# Pluvion_2_-_Rev_B.net
KiCad netlist of a schematic drawn in EAGLE
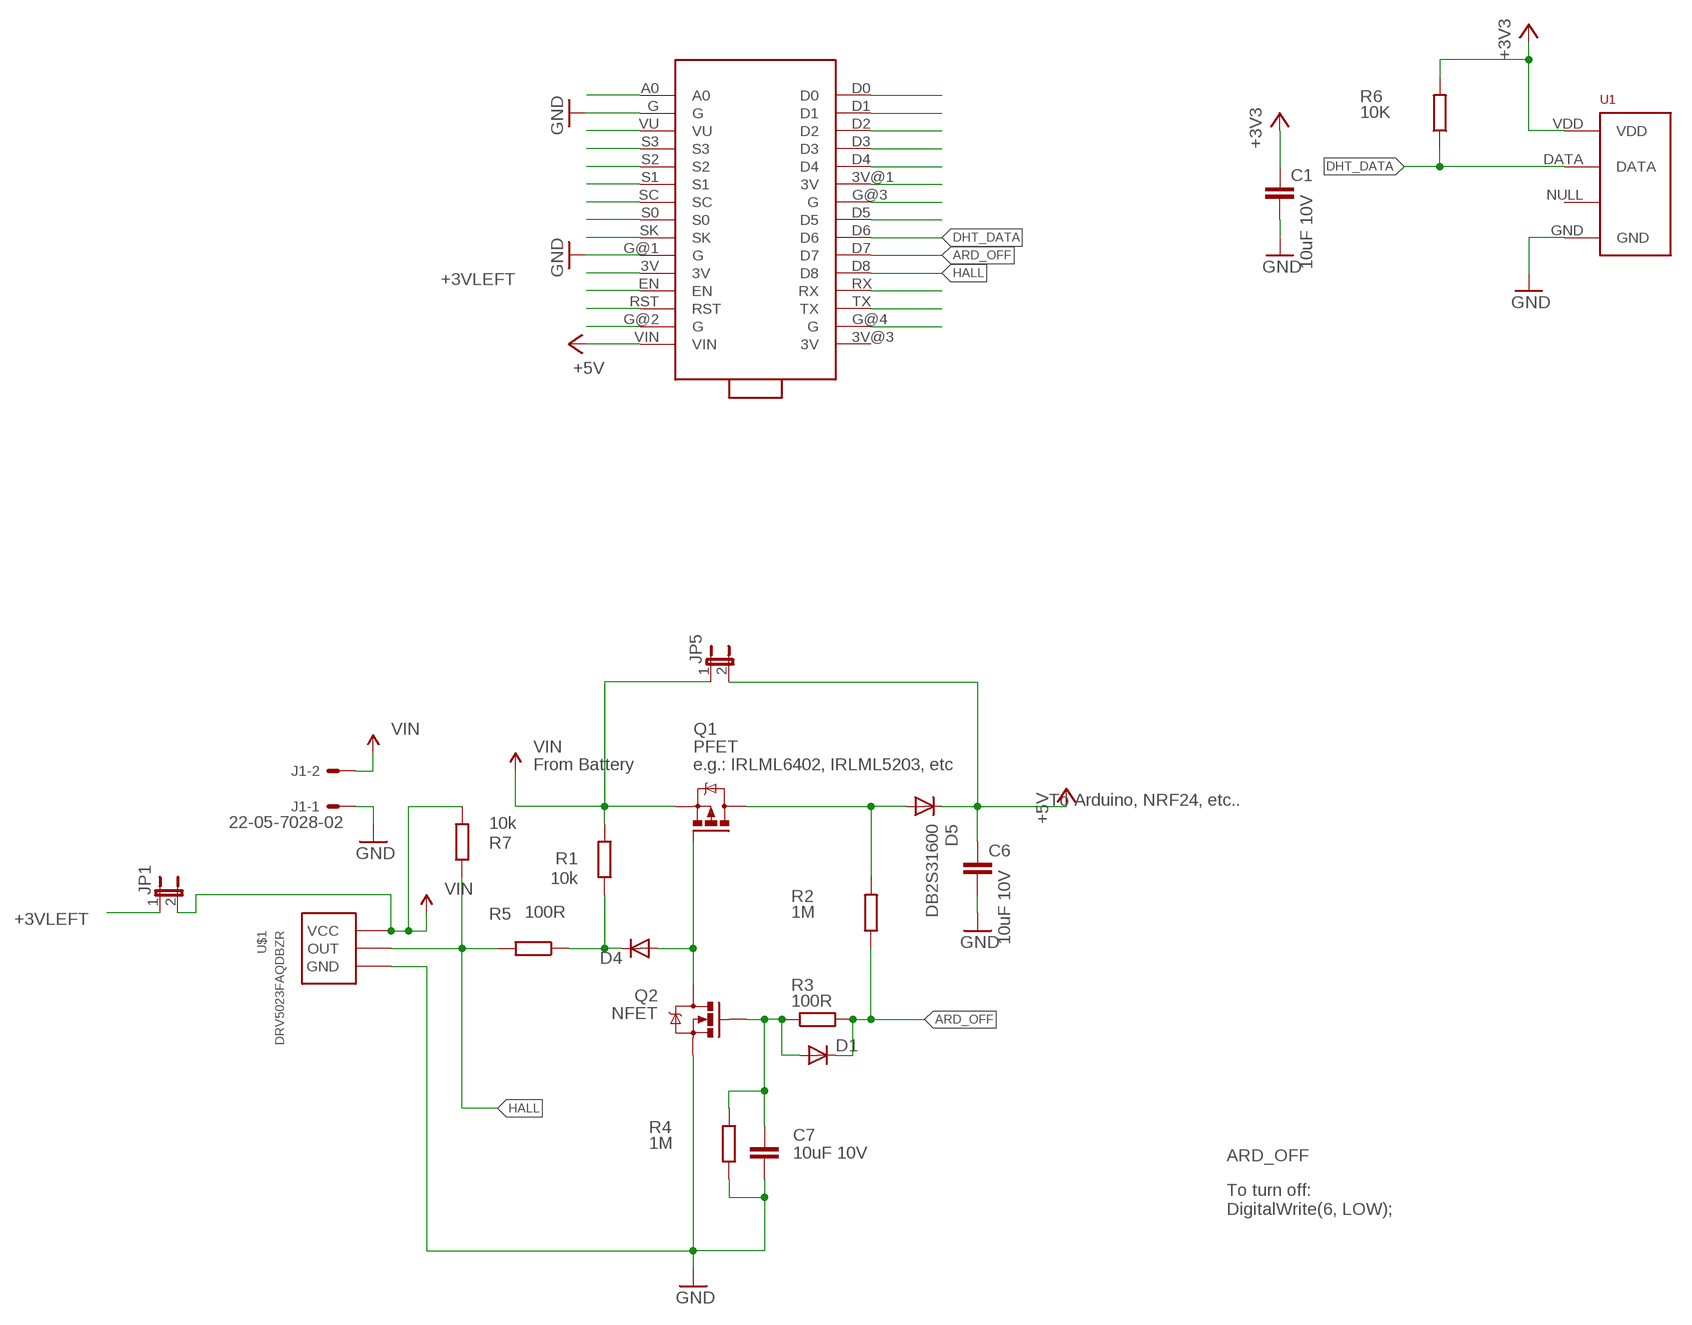
[diagram p0: schematic, sheet 1]

(export (version "E")
  (design (tool "Eeschema 10.0.6"))
  (components
    (comp (ref "C1")
      (value "10uF 10V")
      (footprint "eagle-import:C0805")
      (libsource (lib "eagle-import") (part "C-EUC0805"))
    )
    (comp (ref "C6")
      (value "10uF 10V")
      (footprint "eagle-import:C0805")
      (libsource (lib "eagle-import") (part "C-EUC0805"))
    )
    (comp (ref "C7")
      (value "10uF 10V")
      (footprint "eagle-import:C0805")
      (libsource (lib "eagle-import") (part "C-EUC0805"))
    )
    (comp (ref "D1")
      (value "DIODESOD")
      (footprint "eagle-import:SOD-323")
      (libsource (lib "eagle-import") (part "DIODESOD"))
    )
    (comp (ref "D4")
      (value "DIODESOD")
      (footprint "eagle-import:SOD-323")
      (libsource (lib "eagle-import") (part "DIODESOD"))
    )
    (comp (ref "D5")
      (value "DB2S31600")
      (footprint "eagle-import:SMA-DIODE")
      (libsource (lib "eagle-import") (part "DIODESMA"))
    )
    (comp (ref "J1")
      (value "22-05-7028-02")
      (footprint "eagle-import:7395-02")
      (libsource (lib "eagle-import") (part "22-?-0205-7028"))
    )
    (comp (ref "JP1")
      (value "JUMPER-2PTH")
      (footprint "eagle-import:1X02")
      (libsource (lib "eagle-import") (part "JUMPER-2PTH"))
    )
    (comp (ref "JP5")
      (value "JUMPER-2PTH")
      (footprint "eagle-import:1X02")
      (libsource (lib "eagle-import") (part "JUMPER-2PTH"))
    )
    (comp (ref "Q1")
      (value "PFET")
      (footprint "eagle-import:MICRO3")
      (libsource (lib "eagle-import") (part "IRLML5203"))
    )
    (comp (ref "Q2")
      (value "NFET")
      (footprint "eagle-import:SOT23")
      (libsource (lib "eagle-import") (part "MOSFET-NCHANNELBSS123LT1G"))
    )
    (comp (ref "R1")
      (value "10k")
      (footprint "eagle-import:R0805")
      (libsource (lib "eagle-import") (part "R-EU_R0805"))
    )
    (comp (ref "R2")
      (value "1M")
      (footprint "eagle-import:R0805")
      (libsource (lib "eagle-import") (part "R-EU_R0805"))
    )
    (comp (ref "R3")
      (value "100R")
      (footprint "eagle-import:R0805")
      (libsource (lib "eagle-import") (part "R-EU_R0805"))
    )
    (comp (ref "R4")
      (value "1M")
      (footprint "eagle-import:R0805")
      (libsource (lib "eagle-import") (part "R-EU_R0805"))
    )
    (comp (ref "R5")
      (value "100R")
      (footprint "eagle-import:R0805")
      (libsource (lib "eagle-import") (part "R-EU_R0805"))
    )
    (comp (ref "R6")
      (value "10K")
      (footprint "eagle-import:R0805")
      (libsource (lib "eagle-import") (part "R-EU_R0805"))
    )
    (comp (ref "R7")
      (value "10k")
      (footprint "eagle-import:R0805")
      (libsource (lib "eagle-import") (part "R-EU_R0805"))
    )
    (comp (ref "U$1")
      (value "DRV5023FAQDBZR")
      (footprint "eagle-import:SOT23")
      (libsource (lib "eagle-import") (part "DRV5023FAQDBZR"))
    )
    (comp (ref "U$2")
      (value "NODE-LOLIN-ESP8266")
      (footprint "eagle-import:NODE-LOLIN-ESP8266")
      (libsource (lib "eagle-import") (part "NODE-LOLIN-ESP8266"))
    )
    (comp (ref "U1")
      (value "RHT03_DHT-22_AM2302RA")
      (footprint "eagle-import:RHT03_DHT-22_RA")
      (libsource (lib "eagle-import") (part "RHT03_DHT-22_AM2302RA"))
    )
  )
  (nets
    (net (code "1") (name "+3V3") (class "Default")
      (node (ref "C1") (pin "1") (pinfunction "1_1") (pintype "passive"))
      (node (ref "R6") (pin "2") (pinfunction "2_2") (pintype "passive"))
      (node (ref "U$2") (pin "3V@1") (pinfunction "3V_3V@1") (pintype "bidirectional"))
      (node (ref "U1") (pin "VDD") (pinfunction "VDD_VDD") (pintype "power_in"))
    )
    (net (code "2") (name "+3VLEFT") (class "Default")
      (node (ref "JP1") (pin "1") (pinfunction "1_1") (pintype "passive"))
      (node (ref "U$2") (pin "3V") (pinfunction "3V_3V") (pintype "bidirectional"))
    )
    (net (code "3") (name "+5V") (class "Default")
      (node (ref "C6") (pin "1") (pinfunction "1_1") (pintype "passive"))
      (node (ref "D5") (pin "C") (pinfunction "C_C") (pintype "passive"))
      (node (ref "JP5") (pin "2") (pinfunction "2_2") (pintype "passive"))
      (node (ref "U$2") (pin "VIN") (pinfunction "VIN_VIN") (pintype "bidirectional"))
    )
    (net (code "4") (name "ARD_OFF") (class "Default")
      (node (ref "D1") (pin "1") (pinfunction "C_1") (pintype "passive"))
      (node (ref "R2") (pin "1") (pinfunction "1_1") (pintype "passive"))
      (node (ref "R3") (pin "2") (pinfunction "2_2") (pintype "passive"))
      (node (ref "U$2") (pin "D7") (pinfunction "D7_D7") (pintype "bidirectional"))
    )
    (net (code "5") (name "DHT_DATA") (class "Default")
      (node (ref "R6") (pin "1") (pinfunction "1_1") (pintype "passive"))
      (node (ref "U$2") (pin "D6") (pinfunction "D6_D6") (pintype "bidirectional"))
      (node (ref "U1") (pin "DATA") (pinfunction "DATA_DATA") (pintype "bidirectional"))
    )
    (net (code "6") (name "GND") (class "Default")
      (node (ref "C1") (pin "2") (pinfunction "2_2") (pintype "passive"))
      (node (ref "C6") (pin "2") (pinfunction "2_2") (pintype "passive"))
      (node (ref "C7") (pin "2") (pinfunction "2_2") (pintype "passive"))
      (node (ref "J1") (pin "1") (pinfunction "S_1") (pintype "passive"))
      (node (ref "Q2") (pin "2") (pinfunction "S_2") (pintype "passive"))
      (node (ref "R4") (pin "1") (pinfunction "1_1") (pintype "passive"))
      (node (ref "U$1") (pin "3") (pinfunction "GND_3") (pintype "bidirectional"))
      (node (ref "U$2") (pin "G") (pinfunction "G_G") (pintype "bidirectional"))
      (node (ref "U$2") (pin "G@1") (pinfunction "G_G@1") (pintype "bidirectional"))
      (node (ref "U1") (pin "GND") (pinfunction "GND_GND") (pintype "power_in"))
    )
    (net (code "7") (name "HALL") (class "Default")
      (node (ref "R5") (pin "2") (pinfunction "2_2") (pintype "passive"))
      (node (ref "R7") (pin "2") (pinfunction "2_2") (pintype "passive"))
      (node (ref "U$1") (pin "2") (pinfunction "OUT_2") (pintype "bidirectional"))
      (node (ref "U$2") (pin "D8") (pinfunction "D8_D8") (pintype "bidirectional"))
    )
    (net (code "8") (name "Net-(D1-A)") (class "Default")
      (node (ref "C7") (pin "1") (pinfunction "1_1") (pintype "passive"))
      (node (ref "D1") (pin "2") (pinfunction "A_2") (pintype "passive"))
      (node (ref "Q2") (pin "1") (pinfunction "G_1") (pintype "passive"))
      (node (ref "R3") (pin "1") (pinfunction "1_1") (pintype "passive"))
      (node (ref "R4") (pin "2") (pinfunction "2_2") (pintype "passive"))
    )
    (net (code "9") (name "Net-(D4-A)") (class "Default")
      (node (ref "D4") (pin "2") (pinfunction "A_2") (pintype "passive"))
      (node (ref "Q1") (pin "1") (pinfunction "G_1") (pintype "passive"))
      (node (ref "Q2") (pin "3") (pinfunction "D_3") (pintype "passive"))
    )
    (net (code "10") (name "Net-(D4-C)") (class "Default")
      (node (ref "D4") (pin "1") (pinfunction "C_1") (pintype "passive"))
      (node (ref "R1") (pin "1") (pinfunction "1_1") (pintype "passive"))
      (node (ref "R5") (pin "1") (pinfunction "1_1") (pintype "passive"))
    )
    (net (code "11") (name "Net-(Q1-D)") (class "Default")
      (node (ref "D5") (pin "A") (pinfunction "A_A") (pintype "passive"))
      (node (ref "Q1") (pin "3") (pinfunction "D_3") (pintype "passive"))
      (node (ref "R2") (pin "2") (pinfunction "2_2") (pintype "passive"))
    )
    (net (code "12") (name "VIN") (class "Default")
      (node (ref "J1") (pin "2") (pinfunction "S_2") (pintype "passive"))
      (node (ref "JP1") (pin "2") (pinfunction "2_2") (pintype "passive"))
      (node (ref "JP5") (pin "1") (pinfunction "1_1") (pintype "passive"))
      (node (ref "Q1") (pin "2") (pinfunction "S_2") (pintype "passive"))
      (node (ref "R1") (pin "2") (pinfunction "2_2") (pintype "passive"))
      (node (ref "R7") (pin "1") (pinfunction "1_1") (pintype "passive"))
      (node (ref "U$1") (pin "1") (pinfunction "VCC_1") (pintype "bidirectional"))
    )
    (net (code "13") (name "unconnected-(U$2-3V-Pad3V@3)") (class "Default")
      (node (ref "U$2") (pin "3V@3") (pinfunction "3V_3V@3") (pintype "bidirectional"))
    )
    (net (code "14") (name "unconnected-(U$2-G-PadG@2)") (class "Default")
      (node (ref "U$2") (pin "G@2") (pinfunction "G_G@2") (pintype "bidirectional"))
    )
    (net (code "15") (name "unconnected-(U$2-G-PadG@3)") (class "Default")
      (node (ref "U$2") (pin "G@3") (pinfunction "G_G@3") (pintype "bidirectional"))
    )
    (net (code "16") (name "unconnected-(U$2-G-PadG@4)") (class "Default")
      (node (ref "U$2") (pin "G@4") (pinfunction "G_G@4") (pintype "bidirectional"))
    )
    (net (code "17") (name "unconnected-(U$2-PadA0)") (class "Default")
      (node (ref "U$2") (pin "A0") (pinfunction "A0_A0") (pintype "bidirectional"))
    )
    (net (code "18") (name "unconnected-(U$2-PadD0)") (class "Default")
      (node (ref "U$2") (pin "D0") (pinfunction "D0_D0") (pintype "bidirectional"))
    )
    (net (code "19") (name "unconnected-(U$2-PadD1)") (class "Default")
      (node (ref "U$2") (pin "D1") (pinfunction "D1_D1") (pintype "bidirectional"))
    )
    (net (code "20") (name "unconnected-(U$2-PadD2)") (class "Default")
      (node (ref "U$2") (pin "D2") (pinfunction "D2_D2") (pintype "bidirectional"))
    )
    (net (code "21") (name "unconnected-(U$2-PadD3)") (class "Default")
      (node (ref "U$2") (pin "D3") (pinfunction "D3_D3") (pintype "bidirectional"))
    )
    (net (code "22") (name "unconnected-(U$2-PadD4)") (class "Default")
      (node (ref "U$2") (pin "D4") (pinfunction "D4_D4") (pintype "bidirectional"))
    )
    (net (code "23") (name "unconnected-(U$2-PadD5)") (class "Default")
      (node (ref "U$2") (pin "D5") (pinfunction "D5_D5") (pintype "bidirectional"))
    )
    (net (code "24") (name "unconnected-(U$2-PadEN)") (class "Default")
      (node (ref "U$2") (pin "EN") (pinfunction "EN_EN") (pintype "bidirectional"))
    )
    (net (code "25") (name "unconnected-(U$2-PadRST)") (class "Default")
      (node (ref "U$2") (pin "RST") (pinfunction "RST_RST") (pintype "bidirectional"))
    )
    (net (code "26") (name "unconnected-(U$2-PadRX)") (class "Default")
      (node (ref "U$2") (pin "RX") (pinfunction "RX_RX") (pintype "bidirectional"))
    )
    (net (code "27") (name "unconnected-(U$2-PadS0)") (class "Default")
      (node (ref "U$2") (pin "S0") (pinfunction "S0_S0") (pintype "bidirectional"))
    )
    (net (code "28") (name "unconnected-(U$2-PadS1)") (class "Default")
      (node (ref "U$2") (pin "S1") (pinfunction "S1_S1") (pintype "bidirectional"))
    )
    (net (code "29") (name "unconnected-(U$2-PadS2)") (class "Default")
      (node (ref "U$2") (pin "S2") (pinfunction "S2_S2") (pintype "bidirectional"))
    )
    (net (code "30") (name "unconnected-(U$2-PadS3)") (class "Default")
      (node (ref "U$2") (pin "S3") (pinfunction "S3_S3") (pintype "bidirectional"))
    )
    (net (code "31") (name "unconnected-(U$2-PadSC)") (class "Default")
      (node (ref "U$2") (pin "SC") (pinfunction "SC_SC") (pintype "bidirectional"))
    )
    (net (code "32") (name "unconnected-(U$2-PadSK)") (class "Default")
      (node (ref "U$2") (pin "SK") (pinfunction "SK_SK") (pintype "bidirectional"))
    )
    (net (code "33") (name "unconnected-(U$2-PadTX)") (class "Default")
      (node (ref "U$2") (pin "TX") (pinfunction "TX_TX") (pintype "bidirectional"))
    )
    (net (code "34") (name "unconnected-(U$2-PadVU)") (class "Default")
      (node (ref "U$2") (pin "VU") (pinfunction "VU_VU") (pintype "bidirectional"))
    )
    (net (code "35") (name "unconnected-(U1-PadNULL)") (class "Default")
      (node (ref "U1") (pin "NULL") (pinfunction "NULL_NULL") (pintype "no_connect"))
    )
  )
)
